# Medidas.net
KiCad netlist of a schematic drawn in Altium Designer
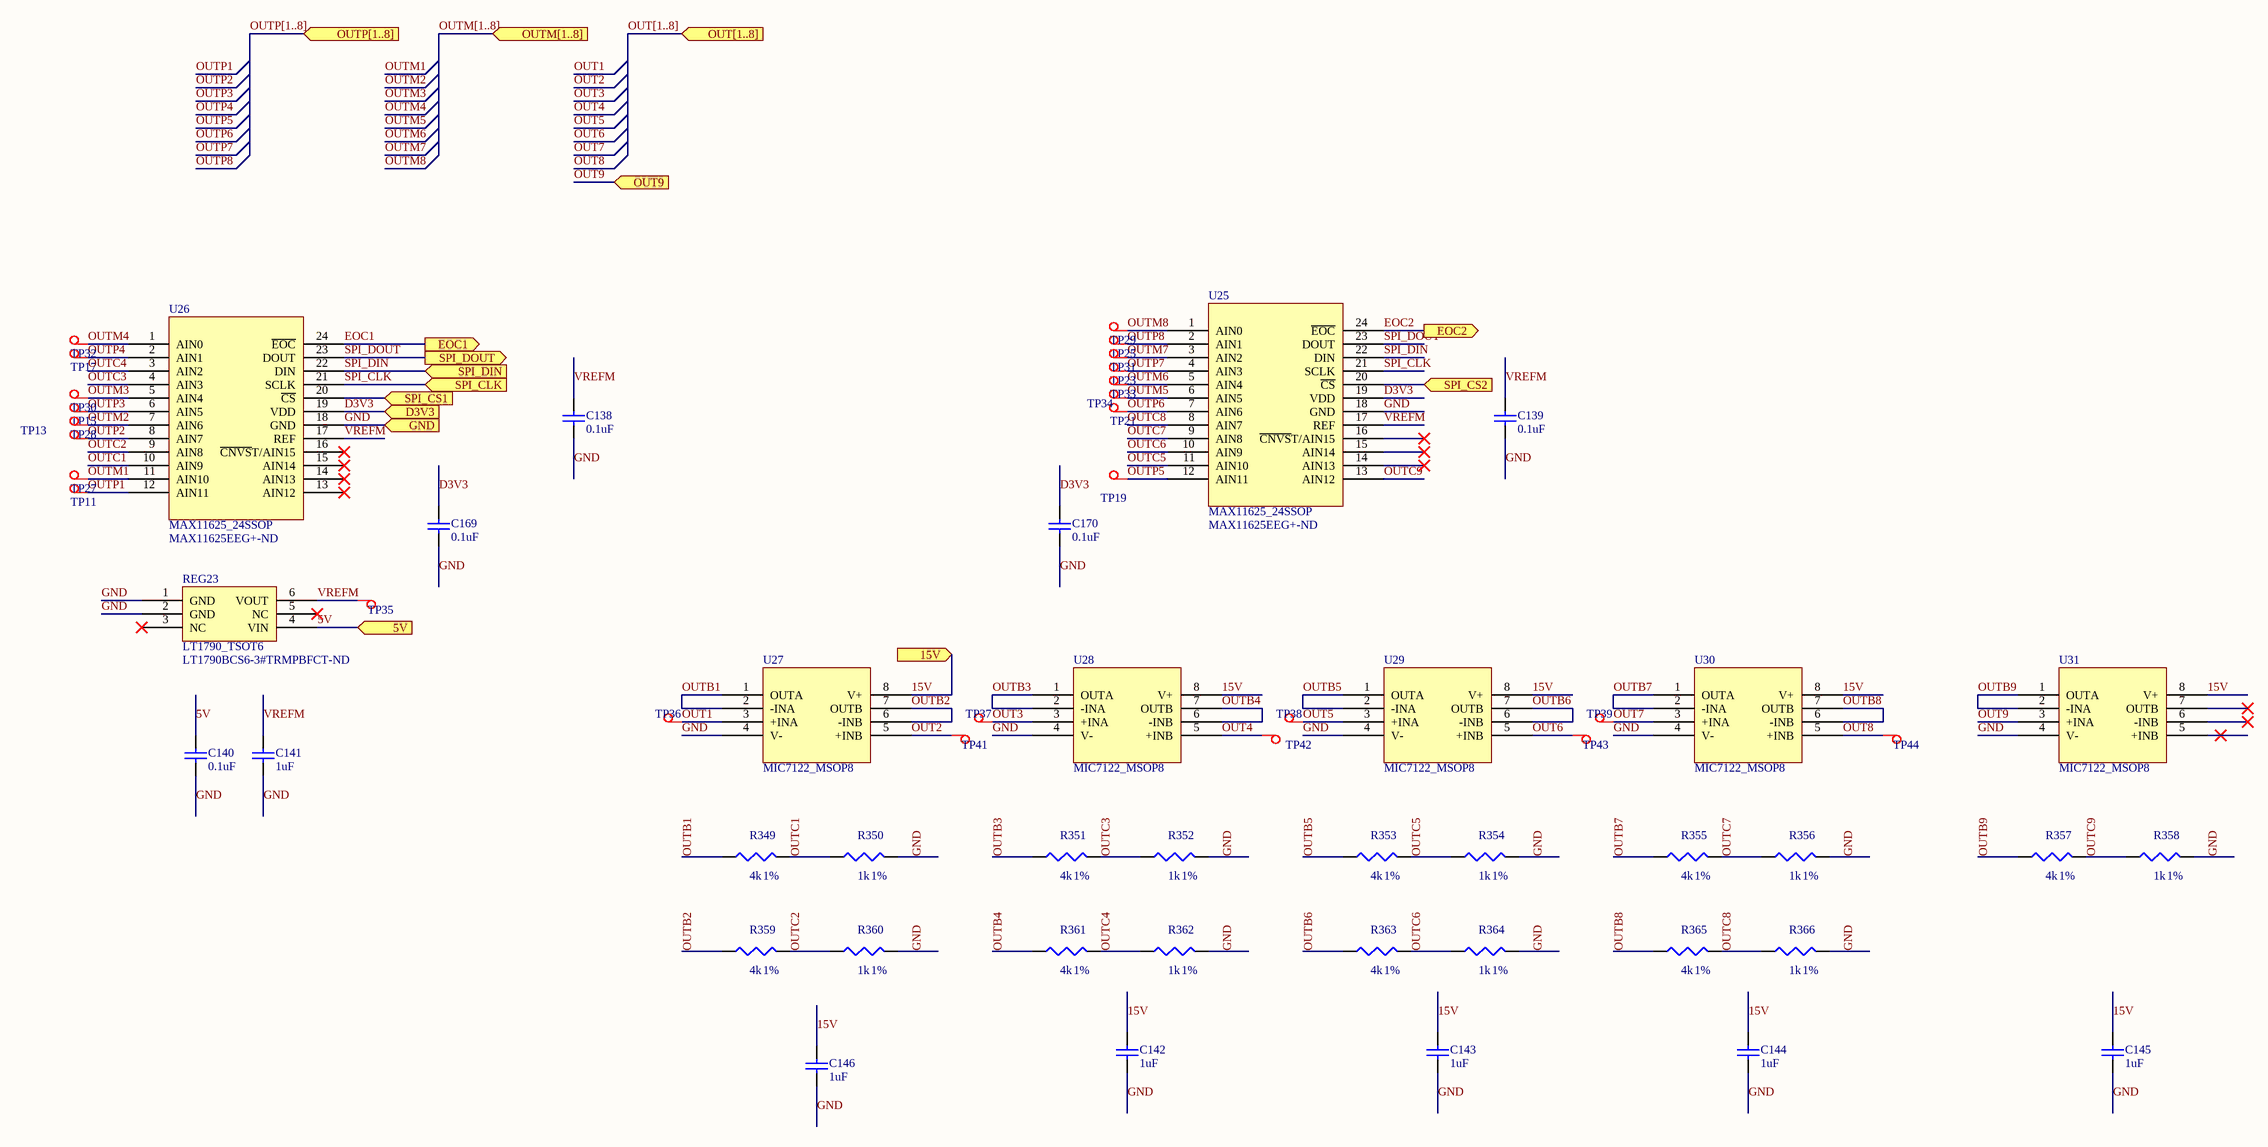
[diagram p0: Medidas.SchDoc]

(export (version "E")
  (design (tool "Eeschema 10.0.6"))
  (components
    (comp (ref "C138")
      (value "0.1uF")
      (footprint "J1-0603")
      (description "Capacitor")
      (fields (field (name "Comment") "Cap") (field (name "PUBLISHER") "Altium Limited"))
      (libsource (lib "Miscellaneous Devices") (part "Cap"))
    )
    (comp (ref "C139")
      (value "0.1uF")
      (footprint "J1-0603")
      (description "Capacitor")
      (fields (field (name "Comment") "Cap") (field (name "PUBLISHER") "Altium Limited"))
      (libsource (lib "Miscellaneous Devices") (part "Cap"))
    )
    (comp (ref "C140")
      (value "0.1uF")
      (footprint "J1-0603")
      (description "Capacitor")
      (fields (field (name "Comment") "Cap") (field (name "PUBLISHER") "Altium Limited"))
      (libsource (lib "Miscellaneous Devices") (part "Cap"))
    )
    (comp (ref "C141")
      (value "1uF")
      (footprint "J1-0603")
      (description "Capacitor")
      (fields (field (name "Comment") "Cap") (field (name "PUBLISHER") "Altium Limited"))
      (libsource (lib "Miscellaneous Devices") (part "Cap"))
    )
    (comp (ref "C142")
      (value "1uF")
      (footprint "J1-0603")
      (description "Capacitor")
      (fields (field (name "Comment") "Cap") (field (name "PUBLISHER") "Altium Limited"))
      (libsource (lib "Miscellaneous Devices") (part "Cap"))
    )
    (comp (ref "C143")
      (value "1uF")
      (footprint "J1-0603")
      (description "Capacitor")
      (fields (field (name "Comment") "Cap") (field (name "PUBLISHER") "Altium Limited"))
      (libsource (lib "Miscellaneous Devices") (part "Cap"))
    )
    (comp (ref "C144")
      (value "1uF")
      (footprint "J1-0603")
      (description "Capacitor")
      (fields (field (name "Comment") "Cap") (field (name "PUBLISHER") "Altium Limited"))
      (libsource (lib "Miscellaneous Devices") (part "Cap"))
    )
    (comp (ref "C145")
      (value "1uF")
      (footprint "J1-0603")
      (description "Capacitor")
      (fields (field (name "Comment") "Cap") (field (name "PUBLISHER") "Altium Limited"))
      (libsource (lib "Miscellaneous Devices") (part "Cap"))
    )
    (comp (ref "C146")
      (value "1uF")
      (footprint "J1-0603")
      (description "Capacitor")
      (fields (field (name "Comment") "Cap") (field (name "PUBLISHER") "Altium Limited"))
      (libsource (lib "Miscellaneous Devices") (part "Cap"))
    )
    (comp (ref "C169")
      (value "0.1uF")
      (footprint "J1-0603")
      (description "Capacitor")
      (fields (field (name "Comment") "Cap") (field (name "PUBLISHER") "Altium Limited"))
      (libsource (lib "Miscellaneous Devices") (part "Cap"))
    )
    (comp (ref "C170")
      (value "0.1uF")
      (footprint "J1-0603")
      (description "Capacitor")
      (fields (field (name "Comment") "Cap") (field (name "PUBLISHER") "Altium Limited"))
      (libsource (lib "Miscellaneous Devices") (part "Cap"))
    )
    (comp (ref "R349")
      (value "4k")
      (footprint "J1-0603")
      (description "Resistor")
      (fields
        (field (name "TOLERANCE") "1%")
        (field (name "Comment") "Res3")
        (field (name "PUBLISHER") "Altium Limited")
      )
      (libsource (lib "Miscellaneous Devices") (part "Res3"))
    )
    (comp (ref "R350")
      (value "1k")
      (footprint "J1-0603")
      (description "Resistor")
      (fields
        (field (name "TOLERANCE") "1%")
        (field (name "Comment") "Res3")
        (field (name "PUBLISHER") "Altium Limited")
      )
      (libsource (lib "Miscellaneous Devices") (part "Res3"))
    )
    (comp (ref "R351")
      (value "4k")
      (footprint "J1-0603")
      (description "Resistor")
      (fields
        (field (name "TOLERANCE") "1%")
        (field (name "Comment") "Res3")
        (field (name "PUBLISHER") "Altium Limited")
      )
      (libsource (lib "Miscellaneous Devices") (part "Res3"))
    )
    (comp (ref "R352")
      (value "1k")
      (footprint "J1-0603")
      (description "Resistor")
      (fields
        (field (name "TOLERANCE") "1%")
        (field (name "Comment") "Res3")
        (field (name "PUBLISHER") "Altium Limited")
      )
      (libsource (lib "Miscellaneous Devices") (part "Res3"))
    )
    (comp (ref "R353")
      (value "4k")
      (footprint "J1-0603")
      (description "Resistor")
      (fields
        (field (name "TOLERANCE") "1%")
        (field (name "Comment") "Res3")
        (field (name "PUBLISHER") "Altium Limited")
      )
      (libsource (lib "Miscellaneous Devices") (part "Res3"))
    )
    (comp (ref "R354")
      (value "1k")
      (footprint "J1-0603")
      (description "Resistor")
      (fields
        (field (name "TOLERANCE") "1%")
        (field (name "Comment") "Res3")
        (field (name "PUBLISHER") "Altium Limited")
      )
      (libsource (lib "Miscellaneous Devices") (part "Res3"))
    )
    (comp (ref "R355")
      (value "4k")
      (footprint "J1-0603")
      (description "Resistor")
      (fields
        (field (name "TOLERANCE") "1%")
        (field (name "Comment") "Res3")
        (field (name "PUBLISHER") "Altium Limited")
      )
      (libsource (lib "Miscellaneous Devices") (part "Res3"))
    )
    (comp (ref "R356")
      (value "1k")
      (footprint "J1-0603")
      (description "Resistor")
      (fields
        (field (name "TOLERANCE") "1%")
        (field (name "Comment") "Res3")
        (field (name "PUBLISHER") "Altium Limited")
      )
      (libsource (lib "Miscellaneous Devices") (part "Res3"))
    )
    (comp (ref "R357")
      (value "4k")
      (footprint "J1-0603")
      (description "Resistor")
      (fields
        (field (name "TOLERANCE") "1%")
        (field (name "Comment") "Res3")
        (field (name "PUBLISHER") "Altium Limited")
      )
      (libsource (lib "Miscellaneous Devices") (part "Res3"))
    )
    (comp (ref "R358")
      (value "1k")
      (footprint "J1-0603")
      (description "Resistor")
      (fields
        (field (name "TOLERANCE") "1%")
        (field (name "Comment") "Res3")
        (field (name "PUBLISHER") "Altium Limited")
      )
      (libsource (lib "Miscellaneous Devices") (part "Res3"))
    )
    (comp (ref "R359")
      (value "4k")
      (footprint "J1-0603")
      (description "Resistor")
      (fields
        (field (name "TOLERANCE") "1%")
        (field (name "Comment") "Res3")
        (field (name "PUBLISHER") "Altium Limited")
      )
      (libsource (lib "Miscellaneous Devices") (part "Res3"))
    )
    (comp (ref "R360")
      (value "1k")
      (footprint "J1-0603")
      (description "Resistor")
      (fields
        (field (name "TOLERANCE") "1%")
        (field (name "Comment") "Res3")
        (field (name "PUBLISHER") "Altium Limited")
      )
      (libsource (lib "Miscellaneous Devices") (part "Res3"))
    )
    (comp (ref "R361")
      (value "4k")
      (footprint "J1-0603")
      (description "Resistor")
      (fields
        (field (name "TOLERANCE") "1%")
        (field (name "Comment") "Res3")
        (field (name "PUBLISHER") "Altium Limited")
      )
      (libsource (lib "Miscellaneous Devices") (part "Res3"))
    )
    (comp (ref "R362")
      (value "1k")
      (footprint "J1-0603")
      (description "Resistor")
      (fields
        (field (name "TOLERANCE") "1%")
        (field (name "Comment") "Res3")
        (field (name "PUBLISHER") "Altium Limited")
      )
      (libsource (lib "Miscellaneous Devices") (part "Res3"))
    )
    (comp (ref "R363")
      (value "4k")
      (footprint "J1-0603")
      (description "Resistor")
      (fields
        (field (name "TOLERANCE") "1%")
        (field (name "Comment") "Res3")
        (field (name "PUBLISHER") "Altium Limited")
      )
      (libsource (lib "Miscellaneous Devices") (part "Res3"))
    )
    (comp (ref "R364")
      (value "1k")
      (footprint "J1-0603")
      (description "Resistor")
      (fields
        (field (name "TOLERANCE") "1%")
        (field (name "Comment") "Res3")
        (field (name "PUBLISHER") "Altium Limited")
      )
      (libsource (lib "Miscellaneous Devices") (part "Res3"))
    )
    (comp (ref "R365")
      (value "4k")
      (footprint "J1-0603")
      (description "Resistor")
      (fields
        (field (name "TOLERANCE") "1%")
        (field (name "Comment") "Res3")
        (field (name "PUBLISHER") "Altium Limited")
      )
      (libsource (lib "Miscellaneous Devices") (part "Res3"))
    )
    (comp (ref "R366")
      (value "1k")
      (footprint "J1-0603")
      (description "Resistor")
      (fields
        (field (name "TOLERANCE") "1%")
        (field (name "Comment") "Res3")
        (field (name "PUBLISHER") "Altium Limited")
      )
      (libsource (lib "Miscellaneous Devices") (part "Res3"))
    )
    (comp (ref "REG23")
      (value "LT1790_TSOT6")
      (footprint "LT1790_TSOT6")
      (fields (field (name "SUPPLIER PART NUMBER 1") "LT1790BCS6-3#TRMPBFCT-ND"))
      (libsource (lib "Lib1") (part "LT1790_TSOT6"))
    )
    (comp (ref "TP11")
      (value "Test Point")
      (footprint "TestPoint")
      (libsource (lib "Lib1") (part "Test Point"))
    )
    (comp (ref "TP13")
      (value "Test Point")
      (footprint "TestPoint")
      (libsource (lib "Lib1") (part "Test Point"))
    )
    (comp (ref "TP15")
      (value "Test Point")
      (footprint "TestPoint")
      (libsource (lib "Lib1") (part "Test Point"))
    )
    (comp (ref "TP17")
      (value "Test Point")
      (footprint "TestPoint")
      (libsource (lib "Lib1") (part "Test Point"))
    )
    (comp (ref "TP19")
      (value "Test Point")
      (footprint "TestPoint")
      (libsource (lib "Lib1") (part "Test Point"))
    )
    (comp (ref "TP21")
      (value "Test Point")
      (footprint "TestPoint")
      (libsource (lib "Lib1") (part "Test Point"))
    )
    (comp (ref "TP23")
      (value "Test Point")
      (footprint "TestPoint")
      (libsource (lib "Lib1") (part "Test Point"))
    )
    (comp (ref "TP25")
      (value "Test Point")
      (footprint "TestPoint")
      (libsource (lib "Lib1") (part "Test Point"))
    )
    (comp (ref "TP27")
      (value "Test Point")
      (footprint "TestPoint")
      (libsource (lib "Lib1") (part "Test Point"))
    )
    (comp (ref "TP28")
      (value "Test Point")
      (footprint "TestPoint")
      (libsource (lib "Lib1") (part "Test Point"))
    )
    (comp (ref "TP29")
      (value "Test Point")
      (footprint "TestPoint")
      (libsource (lib "Lib1") (part "Test Point"))
    )
    (comp (ref "TP30")
      (value "Test Point")
      (footprint "TestPoint")
      (libsource (lib "Lib1") (part "Test Point"))
    )
    (comp (ref "TP31")
      (value "Test Point")
      (footprint "TestPoint")
      (libsource (lib "Lib1") (part "Test Point"))
    )
    (comp (ref "TP32")
      (value "Test Point")
      (footprint "TestPoint")
      (libsource (lib "Lib1") (part "Test Point"))
    )
    (comp (ref "TP33")
      (value "Test Point")
      (footprint "TestPoint")
      (libsource (lib "Lib1") (part "Test Point"))
    )
    (comp (ref "TP34")
      (value "Test Point")
      (footprint "TestPoint")
      (libsource (lib "Lib1") (part "Test Point"))
    )
    (comp (ref "TP35")
      (value "Test Point")
      (footprint "TestPoint")
      (libsource (lib "Lib1") (part "Test Point"))
    )
    (comp (ref "TP36")
      (value "Test Point")
      (footprint "TestPoint")
      (libsource (lib "Lib1") (part "Test Point"))
    )
    (comp (ref "TP37")
      (value "Test Point")
      (footprint "TestPoint")
      (libsource (lib "Lib1") (part "Test Point"))
    )
    (comp (ref "TP38")
      (value "Test Point")
      (footprint "TestPoint")
      (libsource (lib "Lib1") (part "Test Point"))
    )
    (comp (ref "TP39")
      (value "Test Point")
      (footprint "TestPoint")
      (libsource (lib "Lib1") (part "Test Point"))
    )
    (comp (ref "TP41")
      (value "Test Point")
      (footprint "TestPoint")
      (libsource (lib "Lib1") (part "Test Point"))
    )
    (comp (ref "TP42")
      (value "Test Point")
      (footprint "TestPoint")
      (libsource (lib "Lib1") (part "Test Point"))
    )
    (comp (ref "TP43")
      (value "Test Point")
      (footprint "TestPoint")
      (libsource (lib "Lib1") (part "Test Point"))
    )
    (comp (ref "TP44")
      (value "Test Point")
      (footprint "TestPoint")
      (libsource (lib "Lib1") (part "Test Point"))
    )
    (comp (ref "U25")
      (value "MAX11625_24SSOP")
      (footprint "MAX11625_24SSOP")
      (fields (field (name "SUPPLIER PART NUMBER 1") "MAX11625EEG+-ND"))
      (libsource (lib "Lib1") (part "MAX11625_24SSOP"))
    )
    (comp (ref "U26")
      (value "MAX11625_24SSOP")
      (footprint "MAX11625_24SSOP")
      (fields (field (name "SUPPLIER PART NUMBER 1") "MAX11625EEG+-ND"))
      (libsource (lib "Lib1") (part "MAX11625_24SSOP"))
    )
    (comp (ref "U27")
      (value "MIC7122_MSOP8")
      (footprint "MIC7122_MSOP8")
      (libsource (lib "Lib1") (part "MIC7122_MSOP8"))
    )
    (comp (ref "U28")
      (value "MIC7122_MSOP8")
      (footprint "MIC7122_MSOP8")
      (libsource (lib "Lib1") (part "MIC7122_MSOP8"))
    )
    (comp (ref "U29")
      (value "MIC7122_MSOP8")
      (footprint "MIC7122_MSOP8")
      (libsource (lib "Lib1") (part "MIC7122_MSOP8"))
    )
    (comp (ref "U30")
      (value "MIC7122_MSOP8")
      (footprint "MIC7122_MSOP8")
      (libsource (lib "Lib1") (part "MIC7122_MSOP8"))
    )
    (comp (ref "U31")
      (value "MIC7122_MSOP8")
      (footprint "MIC7122_MSOP8")
      (libsource (lib "Lib1") (part "MIC7122_MSOP8"))
    )
  )
  (nets
    (net (code "1") (name "/5V") (class "Default")
      (node (ref "C140") (pin "1") (pinfunction "1_1") (pintype "passive"))
      (node (ref "REG23") (pin "4") (pinfunction "VIN_4") (pintype "passive"))
    )
    (net (code "2") (name "/15V") (class "Default")
      (node (ref "C142") (pin "1") (pinfunction "1_1") (pintype "passive"))
      (node (ref "C143") (pin "1") (pinfunction "1_1") (pintype "passive"))
      (node (ref "C144") (pin "1") (pinfunction "1_1") (pintype "passive"))
      (node (ref "C145") (pin "1") (pinfunction "1_1") (pintype "passive"))
      (node (ref "C146") (pin "1") (pinfunction "1_1") (pintype "passive"))
      (node (ref "U27") (pin "8") (pinfunction "V+_8") (pintype "passive"))
      (node (ref "U28") (pin "8") (pinfunction "V+_8") (pintype "passive"))
      (node (ref "U29") (pin "8") (pinfunction "V+_8") (pintype "passive"))
      (node (ref "U30") (pin "8") (pinfunction "V+_8") (pintype "passive"))
      (node (ref "U31") (pin "8") (pinfunction "V+_8") (pintype "passive"))
    )
    (net (code "3") (name "/D3V3") (class "Default")
      (node (ref "C169") (pin "1") (pinfunction "1_1") (pintype "passive"))
      (node (ref "C170") (pin "1") (pinfunction "1_1") (pintype "passive"))
      (node (ref "U25") (pin "19") (pinfunction "VDD_19") (pintype "passive"))
      (node (ref "U26") (pin "19") (pinfunction "VDD_19") (pintype "passive"))
    )
    (net (code "4") (name "/EOC1") (class "Default")
      (node (ref "U26") (pin "24") (pinfunction "~{EOC}_24") (pintype "passive"))
    )
    (net (code "5") (name "/EOC2") (class "Default")
      (node (ref "U25") (pin "24") (pinfunction "~{EOC}_24") (pintype "passive"))
    )
    (net (code "6") (name "/GND") (class "Default")
      (node (ref "C138") (pin "2") (pinfunction "2_2") (pintype "passive"))
      (node (ref "C139") (pin "2") (pinfunction "2_2") (pintype "passive"))
      (node (ref "C140") (pin "2") (pinfunction "2_2") (pintype "passive"))
      (node (ref "C141") (pin "2") (pinfunction "2_2") (pintype "passive"))
      (node (ref "C142") (pin "2") (pinfunction "2_2") (pintype "passive"))
      (node (ref "C143") (pin "2") (pinfunction "2_2") (pintype "passive"))
      (node (ref "C144") (pin "2") (pinfunction "2_2") (pintype "passive"))
      (node (ref "C145") (pin "2") (pinfunction "2_2") (pintype "passive"))
      (node (ref "C146") (pin "2") (pinfunction "2_2") (pintype "passive"))
      (node (ref "C169") (pin "2") (pinfunction "2_2") (pintype "passive"))
      (node (ref "C170") (pin "2") (pinfunction "2_2") (pintype "passive"))
      (node (ref "R350") (pin "2") (pinfunction "2_2") (pintype "passive"))
      (node (ref "R352") (pin "2") (pinfunction "2_2") (pintype "passive"))
      (node (ref "R354") (pin "2") (pinfunction "2_2") (pintype "passive"))
      (node (ref "R356") (pin "2") (pinfunction "2_2") (pintype "passive"))
      (node (ref "R358") (pin "2") (pinfunction "2_2") (pintype "passive"))
      (node (ref "R360") (pin "2") (pinfunction "2_2") (pintype "passive"))
      (node (ref "R362") (pin "2") (pinfunction "2_2") (pintype "passive"))
      (node (ref "R364") (pin "2") (pinfunction "2_2") (pintype "passive"))
      (node (ref "R366") (pin "2") (pinfunction "2_2") (pintype "passive"))
      (node (ref "REG23") (pin "1") (pinfunction "GND_1") (pintype "passive"))
      (node (ref "REG23") (pin "2") (pinfunction "GND_2") (pintype "passive"))
      (node (ref "U25") (pin "18") (pinfunction "GND_18") (pintype "passive"))
      (node (ref "U26") (pin "18") (pinfunction "GND_18") (pintype "passive"))
      (node (ref "U27") (pin "4") (pinfunction "V-_4") (pintype "passive"))
      (node (ref "U28") (pin "4") (pinfunction "V-_4") (pintype "passive"))
      (node (ref "U29") (pin "4") (pinfunction "V-_4") (pintype "passive"))
      (node (ref "U30") (pin "4") (pinfunction "V-_4") (pintype "passive"))
      (node (ref "U31") (pin "4") (pinfunction "V-_4") (pintype "passive"))
    )
    (net (code "7") (name "/OUT1") (class "Default")
      (node (ref "TP36") (pin "1") (pinfunction "TP_1") (pintype "passive"))
      (node (ref "U27") (pin "3") (pinfunction "+INA_3") (pintype "passive"))
    )
    (net (code "8") (name "/OUT2") (class "Default")
      (node (ref "TP41") (pin "1") (pinfunction "TP_1") (pintype "passive"))
      (node (ref "U27") (pin "5") (pinfunction "+INB_5") (pintype "passive"))
    )
    (net (code "9") (name "/OUT3") (class "Default")
      (node (ref "TP37") (pin "1") (pinfunction "TP_1") (pintype "passive"))
      (node (ref "U28") (pin "3") (pinfunction "+INA_3") (pintype "passive"))
    )
    (net (code "10") (name "/OUT4") (class "Default")
      (node (ref "TP42") (pin "1") (pinfunction "TP_1") (pintype "passive"))
      (node (ref "U28") (pin "5") (pinfunction "+INB_5") (pintype "passive"))
    )
    (net (code "11") (name "/OUT5") (class "Default")
      (node (ref "TP38") (pin "1") (pinfunction "TP_1") (pintype "passive"))
      (node (ref "U29") (pin "3") (pinfunction "+INA_3") (pintype "passive"))
    )
    (net (code "12") (name "/OUT6") (class "Default")
      (node (ref "TP43") (pin "1") (pinfunction "TP_1") (pintype "passive"))
      (node (ref "U29") (pin "5") (pinfunction "+INB_5") (pintype "passive"))
    )
    (net (code "13") (name "/OUT7") (class "Default")
      (node (ref "TP39") (pin "1") (pinfunction "TP_1") (pintype "passive"))
      (node (ref "U30") (pin "3") (pinfunction "+INA_3") (pintype "passive"))
    )
    (net (code "14") (name "/OUT8") (class "Default")
      (node (ref "TP44") (pin "1") (pinfunction "TP_1") (pintype "passive"))
      (node (ref "U30") (pin "5") (pinfunction "+INB_5") (pintype "passive"))
    )
    (net (code "15") (name "/OUT9") (class "Default")
      (node (ref "U31") (pin "3") (pinfunction "+INA_3") (pintype "passive"))
    )
    (net (code "16") (name "/OUTB1") (class "Default")
      (node (ref "R349") (pin "1") (pinfunction "1_1") (pintype "passive"))
      (node (ref "U27") (pin "1") (pinfunction "OUTA_1") (pintype "passive"))
      (node (ref "U27") (pin "2") (pinfunction "-INA_2") (pintype "passive"))
    )
    (net (code "17") (name "/OUTB2") (class "Default")
      (node (ref "R359") (pin "1") (pinfunction "1_1") (pintype "passive"))
      (node (ref "U27") (pin "6") (pinfunction "-INB_6") (pintype "passive"))
      (node (ref "U27") (pin "7") (pinfunction "OUTB_7") (pintype "passive"))
    )
    (net (code "18") (name "/OUTB3") (class "Default")
      (node (ref "R351") (pin "1") (pinfunction "1_1") (pintype "passive"))
      (node (ref "U28") (pin "1") (pinfunction "OUTA_1") (pintype "passive"))
      (node (ref "U28") (pin "2") (pinfunction "-INA_2") (pintype "passive"))
    )
    (net (code "19") (name "/OUTB4") (class "Default")
      (node (ref "R361") (pin "1") (pinfunction "1_1") (pintype "passive"))
      (node (ref "U28") (pin "6") (pinfunction "-INB_6") (pintype "passive"))
      (node (ref "U28") (pin "7") (pinfunction "OUTB_7") (pintype "passive"))
    )
    (net (code "20") (name "/OUTB5") (class "Default")
      (node (ref "R353") (pin "1") (pinfunction "1_1") (pintype "passive"))
      (node (ref "U29") (pin "1") (pinfunction "OUTA_1") (pintype "passive"))
      (node (ref "U29") (pin "2") (pinfunction "-INA_2") (pintype "passive"))
    )
    (net (code "21") (name "/OUTB6") (class "Default")
      (node (ref "R363") (pin "1") (pinfunction "1_1") (pintype "passive"))
      (node (ref "U29") (pin "6") (pinfunction "-INB_6") (pintype "passive"))
      (node (ref "U29") (pin "7") (pinfunction "OUTB_7") (pintype "passive"))
    )
    (net (code "22") (name "/OUTB7") (class "Default")
      (node (ref "R355") (pin "1") (pinfunction "1_1") (pintype "passive"))
      (node (ref "U30") (pin "1") (pinfunction "OUTA_1") (pintype "passive"))
      (node (ref "U30") (pin "2") (pinfunction "-INA_2") (pintype "passive"))
    )
    (net (code "23") (name "/OUTB8") (class "Default")
      (node (ref "R365") (pin "1") (pinfunction "1_1") (pintype "passive"))
      (node (ref "U30") (pin "6") (pinfunction "-INB_6") (pintype "passive"))
      (node (ref "U30") (pin "7") (pinfunction "OUTB_7") (pintype "passive"))
    )
    (net (code "24") (name "/OUTB9") (class "Default")
      (node (ref "R357") (pin "1") (pinfunction "1_1") (pintype "passive"))
      (node (ref "U31") (pin "1") (pinfunction "OUTA_1") (pintype "passive"))
      (node (ref "U31") (pin "2") (pinfunction "-INA_2") (pintype "passive"))
    )
    (net (code "25") (name "/OUTC1") (class "Default")
      (node (ref "R349") (pin "2") (pinfunction "2_2") (pintype "passive"))
      (node (ref "R350") (pin "1") (pinfunction "1_1") (pintype "passive"))
      (node (ref "U26") (pin "10") (pinfunction "AIN9_10") (pintype "passive"))
    )
    (net (code "26") (name "/OUTC2") (class "Default")
      (node (ref "R359") (pin "2") (pinfunction "2_2") (pintype "passive"))
      (node (ref "R360") (pin "1") (pinfunction "1_1") (pintype "passive"))
      (node (ref "U26") (pin "9") (pinfunction "AIN8_9") (pintype "passive"))
    )
    (net (code "27") (name "/OUTC3") (class "Default")
      (node (ref "R351") (pin "2") (pinfunction "2_2") (pintype "passive"))
      (node (ref "R352") (pin "1") (pinfunction "1_1") (pintype "passive"))
      (node (ref "U26") (pin "4") (pinfunction "AIN3_4") (pintype "passive"))
    )
    (net (code "28") (name "/OUTC4") (class "Default")
      (node (ref "R361") (pin "2") (pinfunction "2_2") (pintype "passive"))
      (node (ref "R362") (pin "1") (pinfunction "1_1") (pintype "passive"))
      (node (ref "U26") (pin "3") (pinfunction "AIN2_3") (pintype "passive"))
    )
    (net (code "29") (name "/OUTC5") (class "Default")
      (node (ref "R353") (pin "2") (pinfunction "2_2") (pintype "passive"))
      (node (ref "R354") (pin "1") (pinfunction "1_1") (pintype "passive"))
      (node (ref "U25") (pin "11") (pinfunction "AIN10_11") (pintype "passive"))
    )
    (net (code "30") (name "/OUTC6") (class "Default")
      (node (ref "R363") (pin "2") (pinfunction "2_2") (pintype "passive"))
      (node (ref "R364") (pin "1") (pinfunction "1_1") (pintype "passive"))
      (node (ref "U25") (pin "10") (pinfunction "AIN9_10") (pintype "passive"))
    )
    (net (code "31") (name "/OUTC7") (class "Default")
      (node (ref "R355") (pin "2") (pinfunction "2_2") (pintype "passive"))
      (node (ref "R356") (pin "1") (pinfunction "1_1") (pintype "passive"))
      (node (ref "U25") (pin "9") (pinfunction "AIN8_9") (pintype "passive"))
    )
    (net (code "32") (name "/OUTC8") (class "Default")
      (node (ref "R365") (pin "2") (pinfunction "2_2") (pintype "passive"))
      (node (ref "R366") (pin "1") (pinfunction "1_1") (pintype "passive"))
      (node (ref "U25") (pin "8") (pinfunction "AIN7_8") (pintype "passive"))
    )
    (net (code "33") (name "/OUTC9") (class "Default")
      (node (ref "R357") (pin "2") (pinfunction "2_2") (pintype "passive"))
      (node (ref "R358") (pin "1") (pinfunction "1_1") (pintype "passive"))
      (node (ref "U25") (pin "13") (pinfunction "AIN12_13") (pintype "passive"))
    )
    (net (code "34") (name "/OUTM1") (class "Default")
      (node (ref "TP27") (pin "1") (pinfunction "TP_1") (pintype "passive"))
      (node (ref "U26") (pin "11") (pinfunction "AIN10_11") (pintype "passive"))
    )
    (net (code "35") (name "/OUTM2") (class "Default")
      (node (ref "TP28") (pin "1") (pinfunction "TP_1") (pintype "passive"))
      (node (ref "U26") (pin "7") (pinfunction "AIN6_7") (pintype "passive"))
    )
    (net (code "36") (name "/OUTM3") (class "Default")
      (node (ref "TP30") (pin "1") (pinfunction "TP_1") (pintype "passive"))
      (node (ref "U26") (pin "5") (pinfunction "AIN4_5") (pintype "passive"))
    )
    (net (code "37") (name "/OUTM4") (class "Default")
      (node (ref "TP32") (pin "1") (pinfunction "TP_1") (pintype "passive"))
      (node (ref "U26") (pin "1") (pinfunction "AIN0_1") (pintype "passive"))
    )
    (net (code "38") (name "/OUTM5") (class "Default")
      (node (ref "TP34") (pin "1") (pinfunction "TP_1") (pintype "passive"))
      (node (ref "U25") (pin "6") (pinfunction "AIN5_6") (pintype "passive"))
    )
    (net (code "39") (name "/OUTM6") (class "Default")
      (node (ref "TP33") (pin "1") (pinfunction "TP_1") (pintype "passive"))
      (node (ref "U25") (pin "5") (pinfunction "AIN4_5") (pintype "passive"))
    )
    (net (code "40") (name "/OUTM7") (class "Default")
      (node (ref "TP31") (pin "1") (pinfunction "TP_1") (pintype "passive"))
      (node (ref "U25") (pin "3") (pinfunction "AIN2_3") (pintype "passive"))
    )
    (net (code "41") (name "/OUTM8") (class "Default")
      (node (ref "TP29") (pin "1") (pinfunction "TP_1") (pintype "passive"))
      (node (ref "U25") (pin "1") (pinfunction "AIN0_1") (pintype "passive"))
    )
    (net (code "43") (name "/OUTP1") (class "Default")
      (node (ref "TP11") (pin "1") (pinfunction "TP_1") (pintype "passive"))
      (node (ref "U26") (pin "12") (pinfunction "AIN11_12") (pintype "passive"))
    )
    (net (code "44") (name "/OUTP2") (class "Default")
      (node (ref "TP13") (pin "1") (pinfunction "TP_1") (pintype "passive"))
      (node (ref "U26") (pin "8") (pinfunction "AIN7_8") (pintype "passive"))
    )
    (net (code "45") (name "/OUTP3") (class "Default")
      (node (ref "TP15") (pin "1") (pinfunction "TP_1") (pintype "passive"))
      (node (ref "U26") (pin "6") (pinfunction "AIN5_6") (pintype "passive"))
    )
    (net (code "46") (name "/OUTP4") (class "Default")
      (node (ref "TP17") (pin "1") (pinfunction "TP_1") (pintype "passive"))
      (node (ref "U26") (pin "2") (pinfunction "AIN1_2") (pintype "passive"))
    )
    (net (code "47") (name "/OUTP5") (class "Default")
      (node (ref "TP19") (pin "1") (pinfunction "TP_1") (pintype "passive"))
      (node (ref "U25") (pin "12") (pinfunction "AIN11_12") (pintype "passive"))
    )
    (net (code "48") (name "/OUTP6") (class "Default")
      (node (ref "TP21") (pin "1") (pinfunction "TP_1") (pintype "passive"))
      (node (ref "U25") (pin "7") (pinfunction "AIN6_7") (pintype "passive"))
    )
    (net (code "49") (name "/OUTP7") (class "Default")
      (node (ref "TP23") (pin "1") (pinfunction "TP_1") (pintype "passive"))
      (node (ref "U25") (pin "4") (pinfunction "AIN3_4") (pintype "passive"))
    )
    (net (code "50") (name "/OUTP8") (class "Default")
      (node (ref "TP25") (pin "1") (pinfunction "TP_1") (pintype "passive"))
      (node (ref "U25") (pin "2") (pinfunction "AIN1_2") (pintype "passive"))
    )
    (net (code "53") (name "/SPI_CLK") (class "Default")
      (node (ref "U25") (pin "21") (pinfunction "SCLK_21") (pintype "passive"))
      (node (ref "U26") (pin "21") (pinfunction "SCLK_21") (pintype "passive"))
    )
    (net (code "54") (name "/SPI_CS1") (class "Default")
      (node (ref "U26") (pin "20") (pinfunction "~{CS}_20") (pintype "passive"))
    )
    (net (code "55") (name "/SPI_CS2") (class "Default")
      (node (ref "U25") (pin "20") (pinfunction "~{CS}_20") (pintype "passive"))
    )
    (net (code "56") (name "/SPI_DIN") (class "Default")
      (node (ref "U25") (pin "22") (pinfunction "DIN_22") (pintype "passive"))
      (node (ref "U26") (pin "22") (pinfunction "DIN_22") (pintype "passive"))
    )
    (net (code "57") (name "/SPI_DOUT") (class "Default")
      (node (ref "U25") (pin "23") (pinfunction "DOUT_23") (pintype "passive"))
      (node (ref "U26") (pin "23") (pinfunction "DOUT_23") (pintype "passive"))
    )
    (net (code "58") (name "/VREFM") (class "Default")
      (node (ref "C138") (pin "1") (pinfunction "1_1") (pintype "passive"))
      (node (ref "C139") (pin "1") (pinfunction "1_1") (pintype "passive"))
      (node (ref "C141") (pin "1") (pinfunction "1_1") (pintype "passive"))
      (node (ref "REG23") (pin "6") (pinfunction "VOUT_6") (pintype "passive"))
      (node (ref "TP35") (pin "1") (pinfunction "TP_1") (pintype "passive"))
      (node (ref "U25") (pin "17") (pinfunction "REF_17") (pintype "passive"))
      (node (ref "U26") (pin "17") (pinfunction "REF_17") (pintype "passive"))
    )
    (net (code "59") (name "unconnected-(REG23-NC-Pad3)") (class "Default")
      (node (ref "REG23") (pin "3") (pinfunction "NC_3") (pintype "passive+no_connect"))
    )
    (net (code "60") (name "unconnected-(REG23-NC-Pad5)") (class "Default")
      (node (ref "REG23") (pin "5") (pinfunction "NC_5") (pintype "passive+no_connect"))
    )
    (net (code "61") (name "unconnected-(U25-AIN13-Pad14)") (class "Default")
      (node (ref "U25") (pin "14") (pinfunction "AIN13_14") (pintype "passive+no_connect"))
    )
    (net (code "62") (name "unconnected-(U25-AIN14-Pad15)") (class "Default")
      (node (ref "U25") (pin "15") (pinfunction "AIN14_15") (pintype "passive+no_connect"))
    )
    (net (code "63") (name "unconnected-(U25-~{CNVS}T{slash}AIN15-Pad16)") (class "Default")
      (node (ref "U25") (pin "16") (pinfunction "~{CNVS}T/AIN15_16") (pintype "passive+no_connect"))
    )
    (net (code "64") (name "unconnected-(U26-AIN12-Pad13)") (class "Default")
      (node (ref "U26") (pin "13") (pinfunction "AIN12_13") (pintype "passive+no_connect"))
    )
    (net (code "65") (name "unconnected-(U26-AIN13-Pad14)") (class "Default")
      (node (ref "U26") (pin "14") (pinfunction "AIN13_14") (pintype "passive+no_connect"))
    )
    (net (code "66") (name "unconnected-(U26-AIN14-Pad15)") (class "Default")
      (node (ref "U26") (pin "15") (pinfunction "AIN14_15") (pintype "passive+no_connect"))
    )
    (net (code "67") (name "unconnected-(U26-~{CNVS}T{slash}AIN15-Pad16)") (class "Default")
      (node (ref "U26") (pin "16") (pinfunction "~{CNVS}T/AIN15_16") (pintype "passive+no_connect"))
    )
    (net (code "68") (name "unconnected-(U31-+INB-Pad5)") (class "Default")
      (node (ref "U31") (pin "5") (pinfunction "+INB_5") (pintype "passive+no_connect"))
    )
    (net (code "69") (name "unconnected-(U31--INB-Pad6)") (class "Default")
      (node (ref "U31") (pin "6") (pinfunction "-INB_6") (pintype "passive+no_connect"))
    )
    (net (code "70") (name "unconnected-(U31-OUTB-Pad7)") (class "Default")
      (node (ref "U31") (pin "7") (pinfunction "OUTB_7") (pintype "passive+no_connect"))
    )
  )
)
